# Nusbio_2-FT4222.net
KiCad netlist of a schematic drawn in EAGLE
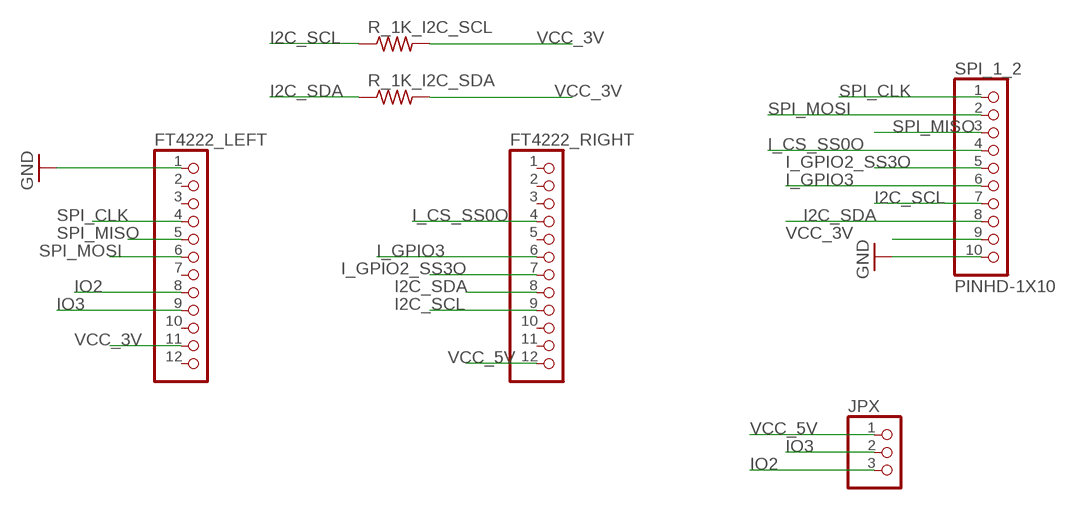
[diagram p0: schematic, sheet 1]

(export (version "E")
  (design (tool "Eeschema 10.0.6"))
  (components
    (comp (ref "FT4222_LEFT")
      (value "PINHD-1X12")
      (footprint "eagle-import:1X12")
      (libsource (lib "eagle-import") (part "PINHD-1X12"))
    )
    (comp (ref "FT4222_RIGHT")
      (value "PINHD-1X12")
      (footprint "eagle-import:1X12")
      (libsource (lib "eagle-import") (part "PINHD-1X12"))
    )
    (comp (ref "JPX")
      (value "PINHD-1X3")
      (footprint "eagle-import:1X03")
      (libsource (lib "eagle-import") (part "PINHD-1X3"))
    )
    (comp (ref "R_1K_I2C_SCL")
      (value "R-US_R1206")
      (footprint "eagle-import:R1206")
      (libsource (lib "eagle-import") (part "R-US_R1206"))
    )
    (comp (ref "R_1K_I2C_SDA")
      (value "R-US_R1206")
      (footprint "eagle-import:R1206")
      (libsource (lib "eagle-import") (part "R-US_R1206"))
    )
    (comp (ref "SPI_1_2")
      (value "PINHD-1X10")
      (footprint "eagle-import:1X10-BIG")
      (libsource (lib "eagle-import") (part "PINHD-1X10"))
    )
  )
  (nets
    (net (code "1") (name "/I2C_SCL") (class "Default")
      (node (ref "FT4222_RIGHT") (pin "9") (pinfunction "9_9") (pintype "passive"))
      (node (ref "R_1K_I2C_SCL") (pin "1") (pinfunction "1_1") (pintype "passive"))
      (node (ref "SPI_1_2") (pin "7") (pinfunction "7_7") (pintype "passive"))
    )
    (net (code "2") (name "/I2C_SDA") (class "Default")
      (node (ref "FT4222_RIGHT") (pin "8") (pinfunction "8_8") (pintype "passive"))
      (node (ref "R_1K_I2C_SDA") (pin "1") (pinfunction "1_1") (pintype "passive"))
      (node (ref "SPI_1_2") (pin "8") (pinfunction "8_8") (pintype "passive"))
    )
    (net (code "3") (name "/IO2") (class "Default")
      (node (ref "FT4222_LEFT") (pin "8") (pinfunction "8_8") (pintype "passive"))
      (node (ref "JPX") (pin "3") (pinfunction "3_3") (pintype "passive"))
    )
    (net (code "4") (name "/IO3") (class "Default")
      (node (ref "FT4222_LEFT") (pin "9") (pinfunction "9_9") (pintype "passive"))
      (node (ref "JPX") (pin "2") (pinfunction "2_2") (pintype "passive"))
    )
    (net (code "5") (name "/I_CS_SS0O") (class "Default")
      (node (ref "FT4222_RIGHT") (pin "4") (pinfunction "4_4") (pintype "passive"))
      (node (ref "SPI_1_2") (pin "4") (pinfunction "4_4") (pintype "passive"))
    )
    (net (code "6") (name "/I_GPIO2_SS3O") (class "Default")
      (node (ref "FT4222_RIGHT") (pin "7") (pinfunction "7_7") (pintype "passive"))
      (node (ref "SPI_1_2") (pin "5") (pinfunction "5_5") (pintype "passive"))
    )
    (net (code "7") (name "/I_GPIO3") (class "Default")
      (node (ref "FT4222_RIGHT") (pin "6") (pinfunction "6_6") (pintype "passive"))
      (node (ref "SPI_1_2") (pin "6") (pinfunction "6_6") (pintype "passive"))
    )
    (net (code "8") (name "/SPI_CLK") (class "Default")
      (node (ref "FT4222_LEFT") (pin "4") (pinfunction "4_4") (pintype "passive"))
      (node (ref "SPI_1_2") (pin "1") (pinfunction "1_1") (pintype "passive"))
    )
    (net (code "9") (name "/SPI_MISO") (class "Default")
      (node (ref "FT4222_LEFT") (pin "5") (pinfunction "5_5") (pintype "passive"))
      (node (ref "SPI_1_2") (pin "3") (pinfunction "3_3") (pintype "passive"))
    )
    (net (code "10") (name "/SPI_MOSI") (class "Default")
      (node (ref "FT4222_LEFT") (pin "6") (pinfunction "6_6") (pintype "passive"))
      (node (ref "SPI_1_2") (pin "2") (pinfunction "2_2") (pintype "passive"))
    )
    (net (code "11") (name "/VCC_3V") (class "Default")
      (node (ref "FT4222_LEFT") (pin "11") (pinfunction "11_11") (pintype "passive"))
      (node (ref "R_1K_I2C_SCL") (pin "2") (pinfunction "2_2") (pintype "passive"))
      (node (ref "R_1K_I2C_SDA") (pin "2") (pinfunction "2_2") (pintype "passive"))
      (node (ref "SPI_1_2") (pin "9") (pinfunction "9_9") (pintype "passive"))
    )
    (net (code "12") (name "/VCC_5V") (class "Default")
      (node (ref "FT4222_RIGHT") (pin "12") (pinfunction "12_12") (pintype "passive"))
      (node (ref "JPX") (pin "1") (pinfunction "1_1") (pintype "passive"))
    )
    (net (code "13") (name "GND") (class "Default")
      (node (ref "FT4222_LEFT") (pin "1") (pinfunction "1_1") (pintype "passive"))
      (node (ref "SPI_1_2") (pin "10") (pinfunction "10_10") (pintype "passive"))
    )
    (net (code "14") (name "unconnected-(FT4222_LEFT-Pad2)") (class "Default")
      (node (ref "FT4222_LEFT") (pin "2") (pinfunction "2_2") (pintype "passive"))
    )
    (net (code "15") (name "unconnected-(FT4222_LEFT-Pad3)") (class "Default")
      (node (ref "FT4222_LEFT") (pin "3") (pinfunction "3_3") (pintype "passive"))
    )
    (net (code "16") (name "unconnected-(FT4222_LEFT-Pad7)") (class "Default")
      (node (ref "FT4222_LEFT") (pin "7") (pinfunction "7_7") (pintype "passive"))
    )
    (net (code "17") (name "unconnected-(FT4222_LEFT-Pad10)") (class "Default")
      (node (ref "FT4222_LEFT") (pin "10") (pinfunction "10_10") (pintype "passive"))
    )
    (net (code "18") (name "unconnected-(FT4222_LEFT-Pad12)") (class "Default")
      (node (ref "FT4222_LEFT") (pin "12") (pinfunction "12_12") (pintype "passive"))
    )
    (net (code "19") (name "unconnected-(FT4222_RIGHT-Pad1)") (class "Default")
      (node (ref "FT4222_RIGHT") (pin "1") (pinfunction "1_1") (pintype "passive"))
    )
    (net (code "20") (name "unconnected-(FT4222_RIGHT-Pad2)") (class "Default")
      (node (ref "FT4222_RIGHT") (pin "2") (pinfunction "2_2") (pintype "passive"))
    )
    (net (code "21") (name "unconnected-(FT4222_RIGHT-Pad3)") (class "Default")
      (node (ref "FT4222_RIGHT") (pin "3") (pinfunction "3_3") (pintype "passive"))
    )
    (net (code "22") (name "unconnected-(FT4222_RIGHT-Pad5)") (class "Default")
      (node (ref "FT4222_RIGHT") (pin "5") (pinfunction "5_5") (pintype "passive"))
    )
    (net (code "23") (name "unconnected-(FT4222_RIGHT-Pad10)") (class "Default")
      (node (ref "FT4222_RIGHT") (pin "10") (pinfunction "10_10") (pintype "passive"))
    )
    (net (code "24") (name "unconnected-(FT4222_RIGHT-Pad11)") (class "Default")
      (node (ref "FT4222_RIGHT") (pin "11") (pinfunction "11_11") (pintype "passive"))
    )
  )
)
